# pmu.net
KiCad netlist of a schematic drawn in Altium Designer
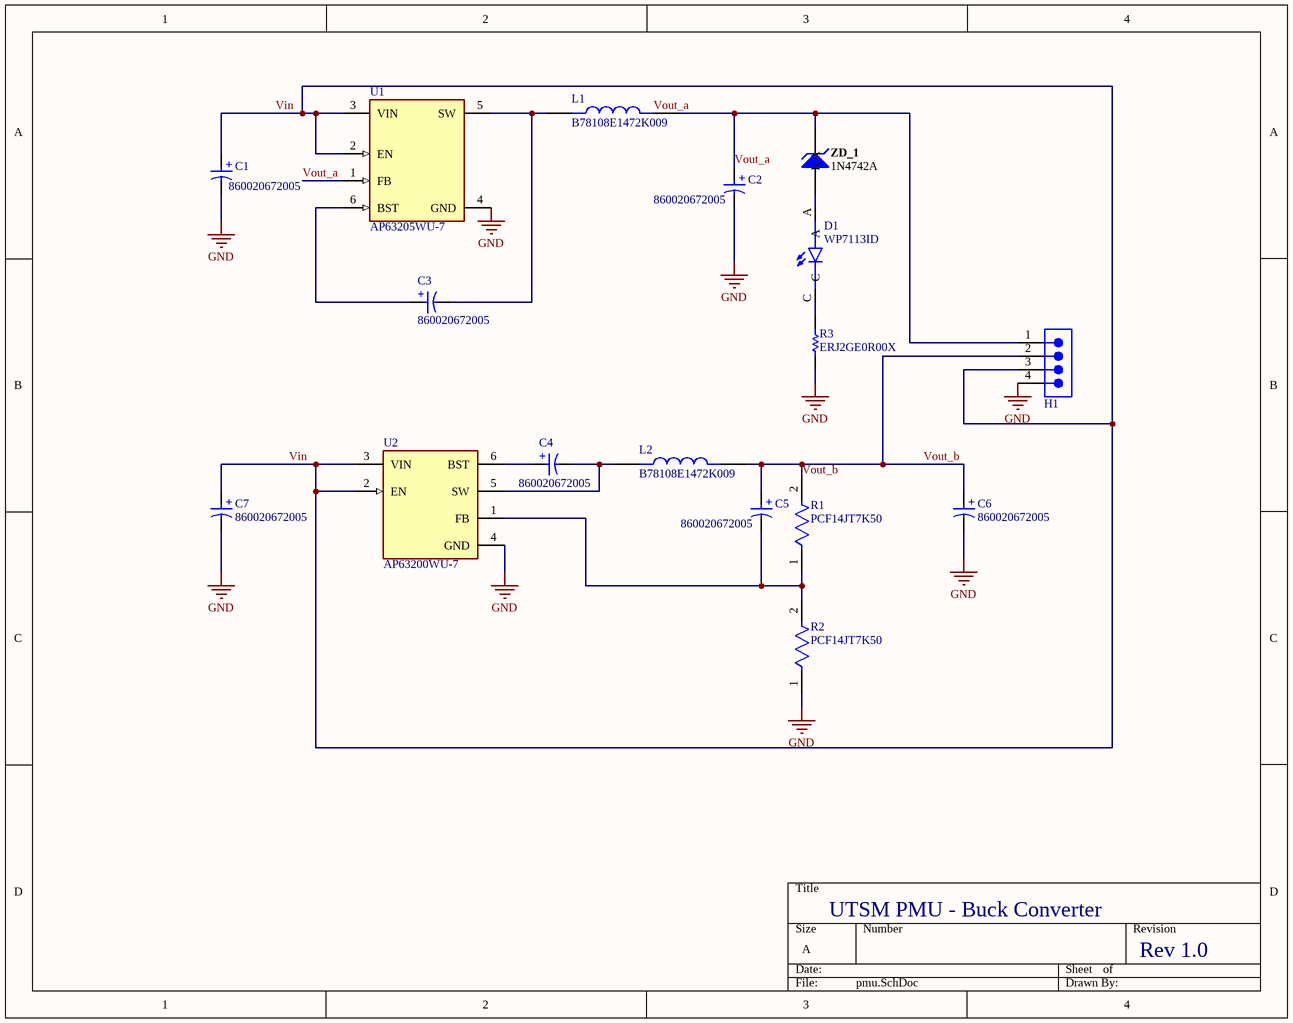
[diagram p0: pmu.SchDoc]

(export (version "E")
  (design (tool "Eeschema 10.0.6"))
  (components
    (comp (ref "C1")
      (value "860020672005")
      (footprint "WCAP-ATG5_D5H11")
      (description "860020672005 WCAP-ATG5 Aluminum Electrolytic Capacitors")
      (fields (field (name "TOLERANCE") "20%"))
      (libsource (lib "Altium Content Vault") (part "Capacitor_Polarized"))
    )
    (comp (ref "C2")
      (value "860020672005")
      (footprint "WCAP-ATG5_D5H11")
      (description "860020672005 WCAP-ATG5 Aluminum Electrolytic Capacitors")
      (fields (field (name "TOLERANCE") "20%"))
      (libsource (lib "Altium Content Vault") (part "Capacitor_Polarized"))
    )
    (comp (ref "C3")
      (value "860020672005")
      (footprint "WCAP-ATG5_D5H11")
      (description "860020672005 WCAP-ATG5 Aluminum Electrolytic Capacitors")
      (fields (field (name "TOLERANCE") "20%"))
      (libsource (lib "Altium Content Vault") (part "Capacitor_Polarized"))
    )
    (comp (ref "C4")
      (value "860020672005")
      (footprint "WCAP-ATG5_D5H11")
      (description "860020672005 WCAP-ATG5 Aluminum Electrolytic Capacitors")
      (fields (field (name "TOLERANCE") "20%"))
      (libsource (lib "Altium Content Vault") (part "Capacitor_Polarized"))
    )
    (comp (ref "C5")
      (value "860020672005")
      (footprint "WCAP-ATG5_D5H11")
      (description "860020672005 WCAP-ATG5 Aluminum Electrolytic Capacitors")
      (fields (field (name "TOLERANCE") "20%"))
      (libsource (lib "Altium Content Vault") (part "Capacitor_Polarized"))
    )
    (comp (ref "C6")
      (value "860020672005")
      (footprint "WCAP-ATG5_D5H11")
      (description "860020672005 WCAP-ATG5 Aluminum Electrolytic Capacitors")
      (fields (field (name "TOLERANCE") "20%"))
      (libsource (lib "Altium Content Vault") (part "Capacitor_Polarized"))
    )
    (comp (ref "C7")
      (value "860020672005")
      (footprint "WCAP-ATG5_D5H11")
      (description "860020672005 WCAP-ATG5 Aluminum Electrolytic Capacitors")
      (fields (field (name "TOLERANCE") "20%"))
      (libsource (lib "Altium Content Vault") (part "Capacitor_Polarized"))
    )
    (comp (ref "D1")
      (value "WP7113ID")
      (footprint "LED_WP7113ID")
      (description "Red 617nm LED Indication - Discrete 2V Radial")
      (fields (field (name "MF") "Kingbright"))
      (libsource (lib "leds-WP7113ID") (part "WP7113ID"))
    )
    (comp (ref "H1")
      (value "61300411121")
      (footprint "61300411121")
      (description "WR-PHD Pin Header, THT, Vertical, pitch 2.54mm, 1 Row, 4P")
      (fields (field (name "MANUFACTURER") "Wurth Elektronik"))
      (libsource (lib "pmu") (part "61300411121"))
    )
    (comp (ref "L1")
      (value "B78108E1472K009")
      (footprint "INDAD1430W80L950D400")
      (description "4.7 ÂµH Unshielded Drum Core, Wirewound Inductor 2.75 A 85mOhm Max Axial")
      (fields (field (name "DIGI-KEY_PART_NUMBER") "495-76025-1-ND") (field (name "MF") "EPCOS"))
      (libsource (lib "B78108E1472K009") (part "B78108E1472K009"))
    )
    (comp (ref "L2")
      (value "B78108E1472K009")
      (footprint "INDAD1430W80L950D400")
      (description "4.7 ÂµH Unshielded Drum Core, Wirewound Inductor 2.75 A 85mOhm Max Axial")
      (fields (field (name "DIGI-KEY_PART_NUMBER") "495-76025-1-ND") (field (name "MF") "EPCOS"))
      (libsource (lib "B78108E1472K009") (part "B78108E1472K009"))
    )
    (comp (ref "R1")
      (value "PCF14JT7K50")
      (footprint "FP-CF14-MFG")
      (description "RES 7.5K OHM 1/4W 5% AXIAL")
      (fields (field (name "TOLERANCE") "5%"))
      (libsource (lib "Altium Content Vault") (part "1029c3af85768c4190bb7ad29bc67b5"))
    )
    (comp (ref "R2")
      (value "PCF14JT7K50")
      (footprint "FP-CF14-MFG")
      (description "RES 7.5K OHM 1/4W 5% AXIAL")
      (fields (field (name "TOLERANCE") "5%"))
      (libsource (lib "Altium Content Vault") (part "1029c3af85768c4190bb7ad29bc67b5"))
    )
    (comp (ref "R3")
      (value "ERJ2GE0R00X")
      (footprint "RESC1005X40X25LL05T05")
      (description "Chip Resistor, 0 Ohm, 0.1 W, -55 to 155 degC, 0402 (1005 Metric), RoHS, Tape and Reel")
      (fields (field (name "MANUFACTURER") "Panasonic") (field (name "TOLERANCE") "5%"))
      (libsource (lib "Altium Content Vault") (part "RES-2"))
    )
    (comp (ref "U1")
      (value "AP63205WU-7")
      (footprint "FP-TSOT26-MFG")
      (description "IC REG BUCK 5V 2A TSOT26")
      (fields
        (field (name "MANUFACTURER") "Diodes Inc.")
        (field (name "OCTOPART") "https://octopart.com/ap63205wu-7-diodes+inc.-98099551")
      )
      (libsource (lib "Altium Content Vault") (part "029bc9fbfa4a99dbb8b3a24c2adb655"))
    )
    (comp (ref "U2")
      (value "AP63200WU-7")
      (footprint "FP-TSOT26-MFG")
      (description "IC REG BUCK ADJUSTABLE 2A TSOT26")
      (fields
        (field (name "OCTOPART") "https://octopart.com/ap63200wu-7-diodes+inc.-98099548")
        (field (name "MANUFACTURER") "Diodes Inc.")
      )
      (libsource (lib "Altium Content Vault") (part "2ae3aed49e7ee94ca813948749813a1"))
    )
    (comp (ref "ZD_1")
      (value "1N4742A")
      (footprint "FAIR-DO-41-2_V")
      (description "Zener Diode, 12V, 1W, 5%, -65 to 200 degC, 2-Pin DO-41, Body 2.72 x 5.2 mm, RoHS")
      (fields (field (name "TOLERANCE") "5%") (field (name "MANUFACTURER") "Fairchild Semiconductor"))
      (libsource (lib "Altium Content Vault") (part "FAIR-DZEN-A1K2-2"))
    )
  )
  (nets
    (net (code "1") (name "/Vin") (class "Default")
      (node (ref "C1") (pin "1") (pinfunction "P_1") (pintype "passive"))
      (node (ref "C7") (pin "1") (pinfunction "P_1") (pintype "passive"))
      (node (ref "H1") (pin "3") (pinfunction "3_3") (pintype "passive"))
      (node (ref "U1") (pin "2") (pinfunction "EN_2") (pintype "input"))
      (node (ref "U1") (pin "3") (pinfunction "VIN_3") (pintype "power_in"))
      (node (ref "U2") (pin "2") (pinfunction "EN_2") (pintype "input"))
      (node (ref "U2") (pin "3") (pinfunction "VIN_3") (pintype "power_in"))
    )
    (net (code "2") (name "/Vout_a") (class "Default")
      (node (ref "C2") (pin "1") (pinfunction "P_1") (pintype "passive"))
      (node (ref "H1") (pin "1") (pinfunction "1_1") (pintype "passive"))
      (node (ref "L1") (pin "2") (pinfunction "2_2") (pintype "passive"))
      (node (ref "U1") (pin "1") (pinfunction "FB_1") (pintype "input"))
      (node (ref "ZD_1") (pin "2") (pinfunction "K_2") (pintype "passive"))
    )
    (net (code "3") (name "/Vout_b") (class "Default")
      (node (ref "C5") (pin "1") (pinfunction "P_1") (pintype "passive"))
      (node (ref "C6") (pin "1") (pinfunction "P_1") (pintype "passive"))
      (node (ref "H1") (pin "2") (pinfunction "2_2") (pintype "passive"))
      (node (ref "L2") (pin "2") (pinfunction "2_2") (pintype "passive"))
      (node (ref "R1") (pin "2") (pinfunction "2_2") (pintype "passive"))
    )
    (net (code "4") (name "GND") (class "Default")
      (node (ref "C1") (pin "2") (pinfunction "N_2") (pintype "passive"))
      (node (ref "C2") (pin "2") (pinfunction "N_2") (pintype "passive"))
      (node (ref "C6") (pin "2") (pinfunction "N_2") (pintype "passive"))
      (node (ref "C7") (pin "2") (pinfunction "N_2") (pintype "passive"))
      (node (ref "H1") (pin "4") (pinfunction "4_4") (pintype "passive"))
      (node (ref "R2") (pin "1") (pinfunction "1_1") (pintype "passive"))
      (node (ref "R3") (pin "1") (pinfunction "1_1") (pintype "passive"))
      (node (ref "U1") (pin "4") (pinfunction "GND_4") (pintype "power_in"))
      (node (ref "U2") (pin "4") (pinfunction "GND_4") (pintype "power_in"))
    )
    (net (code "5") (name "Net-(C3-N)") (class "Default")
      (node (ref "C3") (pin "2") (pinfunction "N_2") (pintype "passive"))
      (node (ref "L1") (pin "1") (pinfunction "1_1") (pintype "passive"))
      (node (ref "U1") (pin "5") (pinfunction "SW_5") (pintype "power_in"))
    )
    (net (code "6") (name "Net-(C3-P)") (class "Default")
      (node (ref "C3") (pin "1") (pinfunction "P_1") (pintype "passive"))
      (node (ref "U1") (pin "6") (pinfunction "BST_6") (pintype "input"))
    )
    (net (code "7") (name "Net-(C4-N)") (class "Default")
      (node (ref "C4") (pin "2") (pinfunction "N_2") (pintype "passive"))
      (node (ref "L2") (pin "1") (pinfunction "1_1") (pintype "passive"))
      (node (ref "U2") (pin "5") (pinfunction "SW_5") (pintype "passive"))
    )
    (net (code "8") (name "Net-(C4-P)") (class "Default")
      (node (ref "C4") (pin "1") (pinfunction "P_1") (pintype "passive"))
      (node (ref "U2") (pin "6") (pinfunction "BST_6") (pintype "passive"))
    )
    (net (code "9") (name "Net-(C5-N)") (class "Default")
      (node (ref "C5") (pin "2") (pinfunction "N_2") (pintype "passive"))
      (node (ref "R1") (pin "1") (pinfunction "1_1") (pintype "passive"))
      (node (ref "R2") (pin "2") (pinfunction "2_2") (pintype "passive"))
      (node (ref "U2") (pin "1") (pinfunction "FB_1") (pintype "passive"))
    )
    (net (code "10") (name "Net-(D1-PadC)") (class "Default")
      (node (ref "D1") (pin "C") (pinfunction "C_C") (pintype "passive"))
      (node (ref "R3") (pin "2") (pinfunction "2_2") (pintype "passive"))
    )
    (net (code "11") (name "Net-(ZD_1-A)") (class "Default")
      (node (ref "D1") (pin "A") (pinfunction "A_A") (pintype "passive"))
      (node (ref "ZD_1") (pin "1") (pinfunction "A_1") (pintype "passive"))
    )
  )
)
